# RTL8812AU.net
KiCad netlist of a schematic drawn in Altium Designer
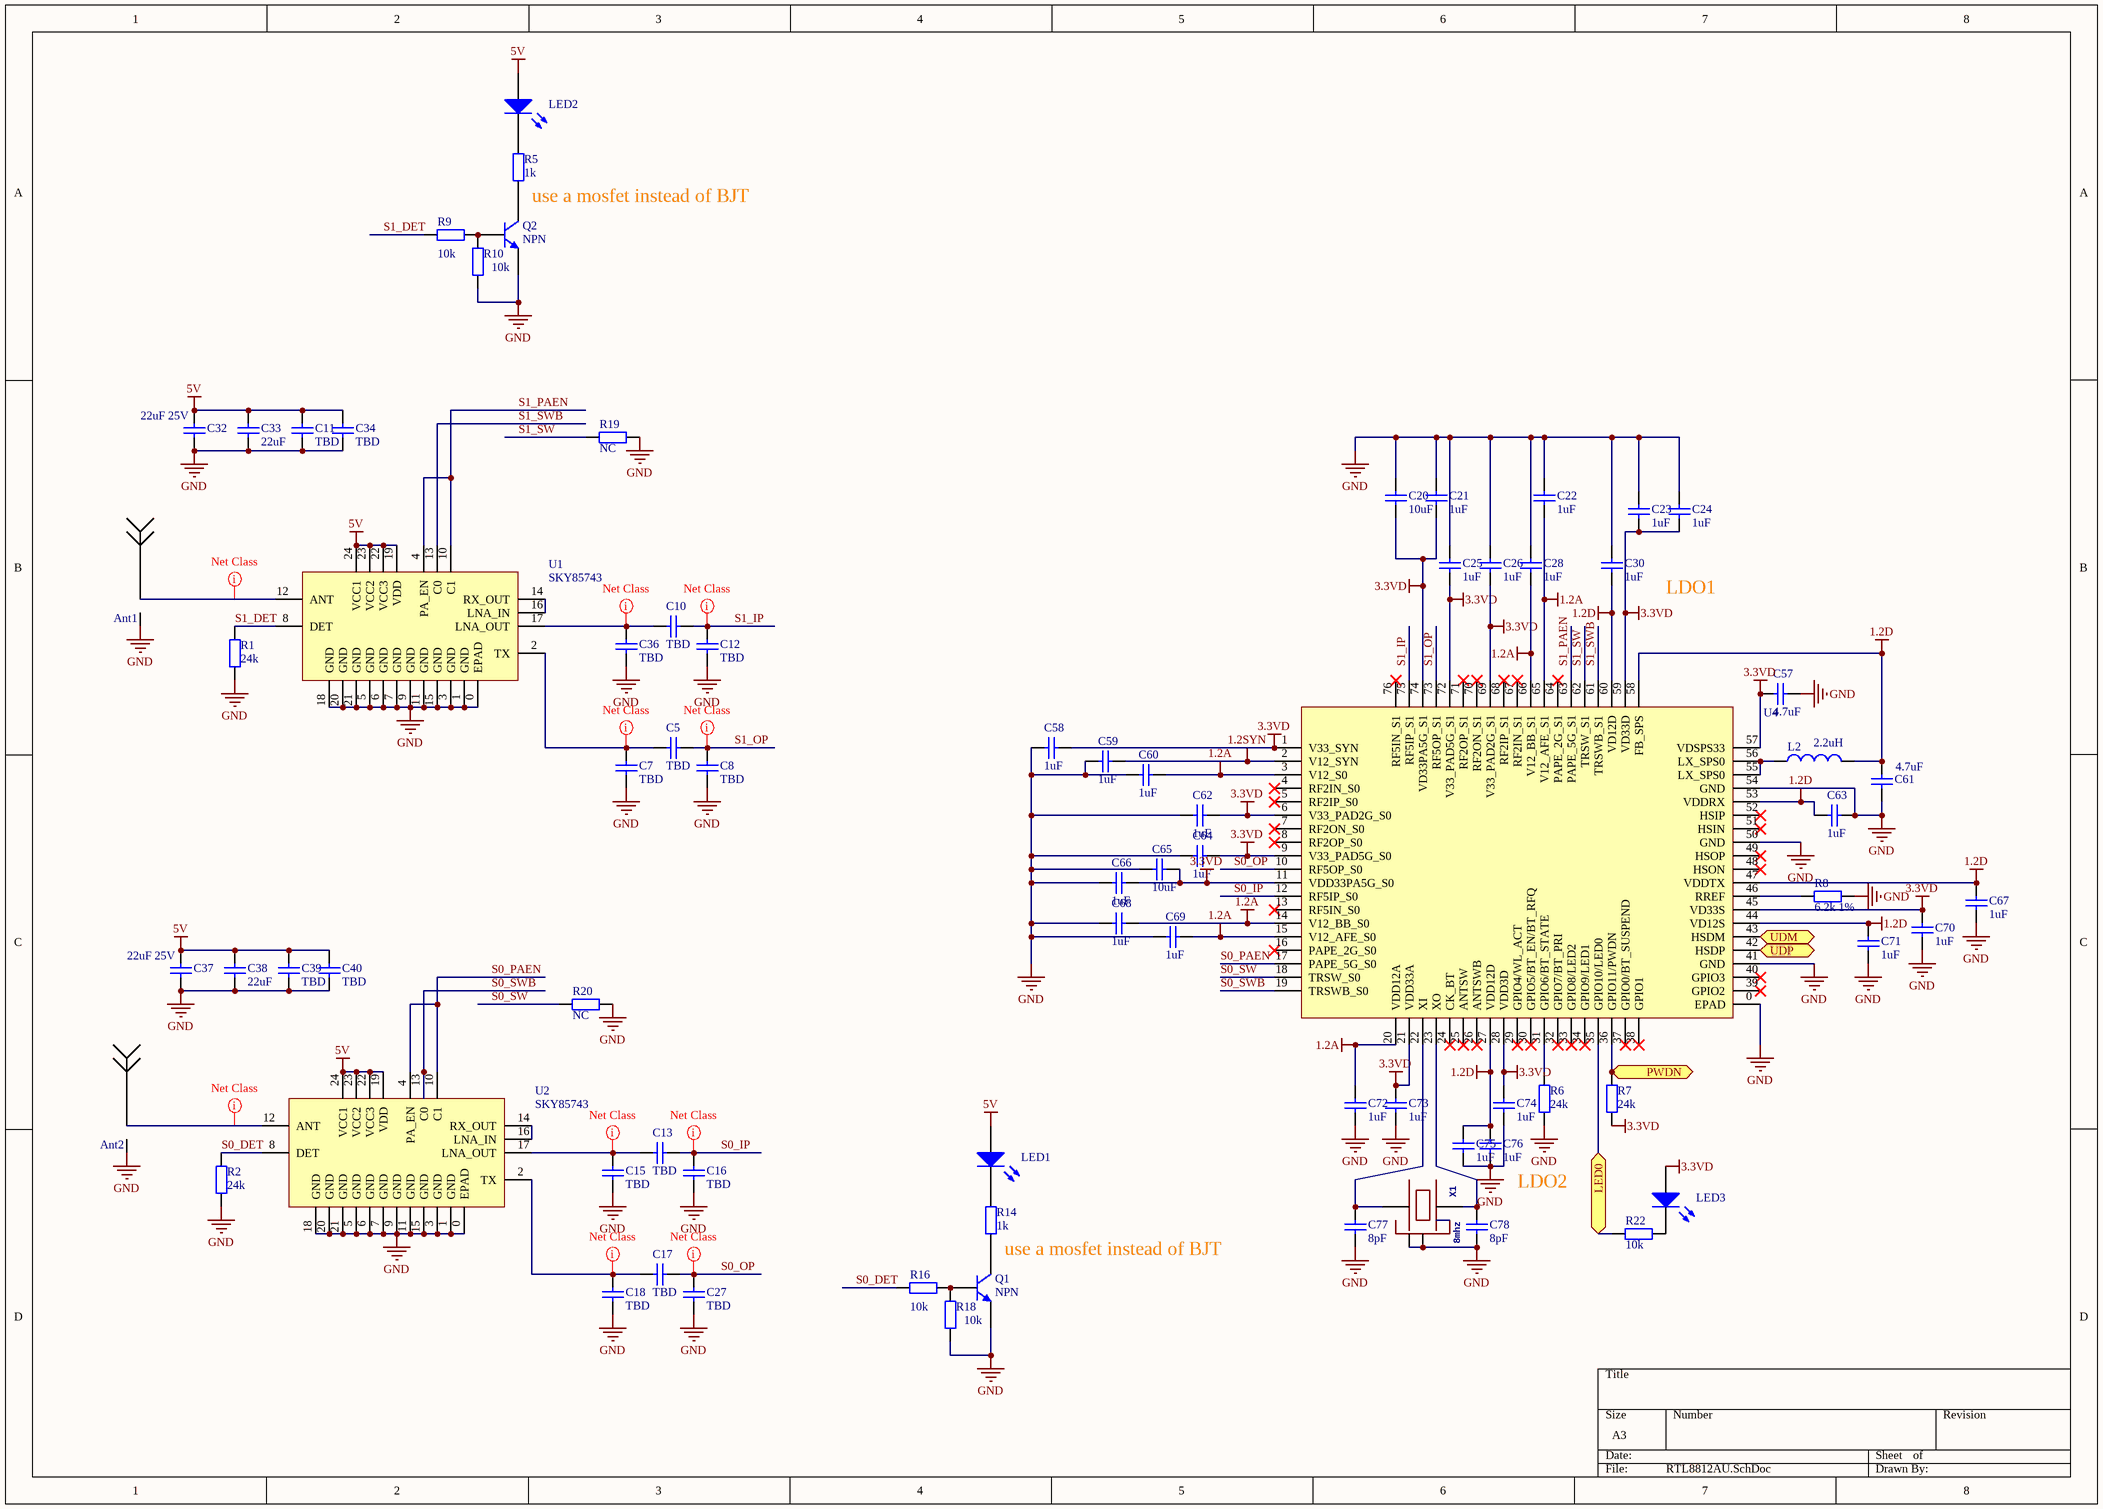
[diagram p0: RTL8812AU.SchDoc]

(export (version "E")
  (design (tool "Eeschema 10.0.6"))
  (components
    (comp (ref "Ant1") (value "Antenna") (footprint "SMA-2") (libsource (lib "F4SDR") (part "Antenna")))
    (comp (ref "Ant2") (value "Antenna") (footprint "SMA-2") (libsource (lib "F4SDR") (part "Antenna")))
    (comp (ref "C5")
      (value "TBD")
      (footprint "0402")
      (description "Capacitor")
      (fields (field (name "PUBLISHER") "Altium Limited"))
      (libsource (lib "RTC6705") (part "Cap"))
    )
    (comp (ref "C7")
      (value "TBD")
      (footprint "0402")
      (description "Capacitor")
      (fields (field (name "PUBLISHER") "Altium Limited"))
      (libsource (lib "RTC6705") (part "Cap"))
    )
    (comp (ref "C8")
      (value "TBD")
      (footprint "0402")
      (description "Capacitor")
      (fields (field (name "PUBLISHER") "Altium Limited"))
      (libsource (lib "RTC6705") (part "Cap"))
    )
    (comp (ref "C10")
      (value "TBD")
      (footprint "0402")
      (description "Capacitor")
      (fields (field (name "PUBLISHER") "Altium Limited"))
      (libsource (lib "RTC6705") (part "Cap"))
    )
    (comp (ref "C11")
      (value "TBD")
      (footprint "0402")
      (description "Capacitor")
      (fields (field (name "PUBLISHER") "Altium Limited"))
      (libsource (lib "RTC6705") (part "Cap"))
    )
    (comp (ref "C12")
      (value "TBD")
      (footprint "0402")
      (description "Capacitor")
      (fields (field (name "PUBLISHER") "Altium Limited"))
      (libsource (lib "RTC6705") (part "Cap"))
    )
    (comp (ref "C13")
      (value "TBD")
      (footprint "0402")
      (description "Capacitor")
      (fields (field (name "PUBLISHER") "Altium Limited"))
      (libsource (lib "RTC6705") (part "Cap"))
    )
    (comp (ref "C15")
      (value "TBD")
      (footprint "0402")
      (description "Capacitor")
      (fields (field (name "PUBLISHER") "Altium Limited"))
      (libsource (lib "RTC6705") (part "Cap"))
    )
    (comp (ref "C16")
      (value "TBD")
      (footprint "0402")
      (description "Capacitor")
      (fields (field (name "PUBLISHER") "Altium Limited"))
      (libsource (lib "RTC6705") (part "Cap"))
    )
    (comp (ref "C17")
      (value "TBD")
      (footprint "0402")
      (description "Capacitor")
      (fields (field (name "PUBLISHER") "Altium Limited"))
      (libsource (lib "RTC6705") (part "Cap"))
    )
    (comp (ref "C18")
      (value "TBD")
      (footprint "0402")
      (description "Capacitor")
      (fields (field (name "PUBLISHER") "Altium Limited"))
      (libsource (lib "RTC6705") (part "Cap"))
    )
    (comp (ref "C20")
      (value "10uF")
      (footprint "0402")
      (description "Capacitor")
      (fields (field (name "PUBLISHER") "Altium Limited"))
      (libsource (lib "RTC6705") (part "Cap"))
    )
    (comp (ref "C21")
      (value "1uF")
      (footprint "0201")
      (description "Capacitor")
      (fields (field (name "PUBLISHER") "Altium Limited"))
      (libsource (lib "RTC6705") (part "Cap"))
    )
    (comp (ref "C22")
      (value "1uF")
      (footprint "0201")
      (description "Capacitor")
      (fields (field (name "PUBLISHER") "Altium Limited"))
      (libsource (lib "RTC6705") (part "Cap"))
    )
    (comp (ref "C23")
      (value "1uF")
      (footprint "0201")
      (description "Capacitor")
      (fields (field (name "PUBLISHER") "Altium Limited"))
      (libsource (lib "RTC6705") (part "Cap"))
    )
    (comp (ref "C24")
      (value "1uF")
      (footprint "0201")
      (description "Capacitor")
      (fields (field (name "PUBLISHER") "Altium Limited"))
      (libsource (lib "RTC6705") (part "Cap"))
    )
    (comp (ref "C25")
      (value "1uF")
      (footprint "0201")
      (description "Capacitor")
      (fields (field (name "PUBLISHER") "Altium Limited"))
      (libsource (lib "RTC6705") (part "Cap"))
    )
    (comp (ref "C26")
      (value "1uF")
      (footprint "0201")
      (description "Capacitor")
      (fields (field (name "PUBLISHER") "Altium Limited"))
      (libsource (lib "RTC6705") (part "Cap"))
    )
    (comp (ref "C27")
      (value "TBD")
      (footprint "0402")
      (description "Capacitor")
      (fields (field (name "PUBLISHER") "Altium Limited"))
      (libsource (lib "RTC6705") (part "Cap"))
    )
    (comp (ref "C28")
      (value "1uF")
      (footprint "0201")
      (description "Capacitor")
      (fields (field (name "PUBLISHER") "Altium Limited"))
      (libsource (lib "RTC6705") (part "Cap"))
    )
    (comp (ref "C30")
      (value "1uF")
      (footprint "0201")
      (description "Capacitor")
      (fields (field (name "PUBLISHER") "Altium Limited"))
      (libsource (lib "RTC6705") (part "Cap"))
    )
    (comp (ref "C32")
      (value "22uF 25V")
      (footprint "1210")
      (description "Capacitor")
      (fields (field (name "Comment") "Cap") (field (name "PUBLISHER") "Altium Limited"))
      (libsource (lib "RTC6705") (part "Cap"))
    )
    (comp (ref "C33")
      (value "22uF")
      (footprint "0805")
      (description "Capacitor")
      (fields (field (name "Comment") "Cap") (field (name "PUBLISHER") "Altium Limited"))
      (libsource (lib "RTC6705") (part "Cap"))
    )
    (comp (ref "C34")
      (value "TBD")
      (footprint "0402")
      (description "Capacitor")
      (fields (field (name "PUBLISHER") "Altium Limited"))
      (libsource (lib "RTC6705") (part "Cap"))
    )
    (comp (ref "C36")
      (value "TBD")
      (footprint "0402")
      (description "Capacitor")
      (fields (field (name "PUBLISHER") "Altium Limited"))
      (libsource (lib "RTC6705") (part "Cap"))
    )
    (comp (ref "C37")
      (value "22uF 25V")
      (footprint "1210")
      (description "Capacitor")
      (fields (field (name "Comment") "Cap") (field (name "PUBLISHER") "Altium Limited"))
      (libsource (lib "RTC6705") (part "Cap"))
    )
    (comp (ref "C38")
      (value "22uF")
      (footprint "0805")
      (description "Capacitor")
      (fields (field (name "Comment") "Cap") (field (name "PUBLISHER") "Altium Limited"))
      (libsource (lib "RTC6705") (part "Cap"))
    )
    (comp (ref "C39")
      (value "TBD")
      (footprint "0402")
      (description "Capacitor")
      (fields (field (name "PUBLISHER") "Altium Limited"))
      (libsource (lib "RTC6705") (part "Cap"))
    )
    (comp (ref "C40")
      (value "TBD")
      (footprint "0402")
      (description "Capacitor")
      (fields (field (name "PUBLISHER") "Altium Limited"))
      (libsource (lib "RTC6705") (part "Cap"))
    )
    (comp (ref "C57")
      (value "4.7uF")
      (footprint "0603")
      (description "Capacitor")
      (fields (field (name "PUBLISHER") "Altium Limited"))
      (libsource (lib "RTC6705") (part "Cap"))
    )
    (comp (ref "C58")
      (value "1uF")
      (footprint "0201")
      (description "Capacitor")
      (fields (field (name "PUBLISHER") "Altium Limited"))
      (libsource (lib "RTC6705") (part "Cap"))
    )
    (comp (ref "C59")
      (value "1uF")
      (footprint "0201")
      (description "Capacitor")
      (fields (field (name "PUBLISHER") "Altium Limited"))
      (libsource (lib "RTC6705") (part "Cap"))
    )
    (comp (ref "C60")
      (value "1uF")
      (footprint "0201")
      (description "Capacitor")
      (fields (field (name "PUBLISHER") "Altium Limited"))
      (libsource (lib "RTC6705") (part "Cap"))
    )
    (comp (ref "C61")
      (value "4.7uF")
      (footprint "0603")
      (description "Capacitor")
      (fields (field (name "PUBLISHER") "Altium Limited"))
      (libsource (lib "RTC6705") (part "Cap"))
    )
    (comp (ref "C62")
      (value "1uF")
      (footprint "0201")
      (description "Capacitor")
      (fields (field (name "PUBLISHER") "Altium Limited"))
      (libsource (lib "RTC6705") (part "Cap"))
    )
    (comp (ref "C63")
      (value "1uF")
      (footprint "0201")
      (description "Capacitor")
      (fields (field (name "PUBLISHER") "Altium Limited"))
      (libsource (lib "RTC6705") (part "Cap"))
    )
    (comp (ref "C64")
      (value "1uF")
      (footprint "0201")
      (description "Capacitor")
      (fields (field (name "PUBLISHER") "Altium Limited"))
      (libsource (lib "RTC6705") (part "Cap"))
    )
    (comp (ref "C65")
      (value "10uF")
      (footprint "0402")
      (description "Capacitor")
      (fields (field (name "PUBLISHER") "Altium Limited"))
      (libsource (lib "RTC6705") (part "Cap"))
    )
    (comp (ref "C66")
      (value "1uF")
      (footprint "0201")
      (description "Capacitor")
      (fields (field (name "PUBLISHER") "Altium Limited"))
      (libsource (lib "RTC6705") (part "Cap"))
    )
    (comp (ref "C67")
      (value "1uF")
      (footprint "0201")
      (description "Capacitor")
      (fields (field (name "PUBLISHER") "Altium Limited"))
      (libsource (lib "RTC6705") (part "Cap"))
    )
    (comp (ref "C68")
      (value "1uF")
      (footprint "0201")
      (description "Capacitor")
      (fields (field (name "PUBLISHER") "Altium Limited"))
      (libsource (lib "RTC6705") (part "Cap"))
    )
    (comp (ref "C69")
      (value "1uF")
      (footprint "0201")
      (description "Capacitor")
      (fields (field (name "PUBLISHER") "Altium Limited"))
      (libsource (lib "RTC6705") (part "Cap"))
    )
    (comp (ref "C70")
      (value "1uF")
      (footprint "0201")
      (description "Capacitor")
      (fields (field (name "PUBLISHER") "Altium Limited"))
      (libsource (lib "RTC6705") (part "Cap"))
    )
    (comp (ref "C71")
      (value "1uF")
      (footprint "0201")
      (description "Capacitor")
      (fields (field (name "PUBLISHER") "Altium Limited"))
      (libsource (lib "RTC6705") (part "Cap"))
    )
    (comp (ref "C72")
      (value "1uF")
      (footprint "0201")
      (description "Capacitor")
      (fields (field (name "PUBLISHER") "Altium Limited"))
      (libsource (lib "RTC6705") (part "Cap"))
    )
    (comp (ref "C73")
      (value "1uF")
      (footprint "0201")
      (description "Capacitor")
      (fields (field (name "PUBLISHER") "Altium Limited"))
      (libsource (lib "RTC6705") (part "Cap"))
    )
    (comp (ref "C74")
      (value "1uF")
      (footprint "0201")
      (description "Capacitor")
      (fields (field (name "PUBLISHER") "Altium Limited"))
      (libsource (lib "RTC6705") (part "Cap"))
    )
    (comp (ref "C75")
      (value "1uF")
      (footprint "0201")
      (description "Capacitor")
      (fields (field (name "PUBLISHER") "Altium Limited"))
      (libsource (lib "RTC6705") (part "Cap"))
    )
    (comp (ref "C76")
      (value "1uF")
      (footprint "0201")
      (description "Capacitor")
      (fields (field (name "PUBLISHER") "Altium Limited"))
      (libsource (lib "RTC6705") (part "Cap"))
    )
    (comp (ref "C77")
      (value "8pF")
      (footprint "0402")
      (description "Capacitor")
      (fields (field (name "PUBLISHER") "Altium Limited"))
      (libsource (lib "RTC6705") (part "Cap"))
    )
    (comp (ref "C78")
      (value "8pF")
      (footprint "0402")
      (description "Capacitor")
      (fields (field (name "PUBLISHER") "Altium Limited"))
      (libsource (lib "RTC6705") (part "Cap"))
    )
    (comp (ref "L2")
      (value "2.2uH")
      (footprint "0806")
      (description "Inductor")
      (fields (field (name "PUBLISHER") "Altium Limited"))
      (libsource (lib "Miscellaneous Devices") (part "Inductor"))
    )
    (comp (ref "LED1")
      (value "LED0")
      (footprint "0603")
      (description "Typical INFRARED GaAs LED")
      (fields (field (name "PUBLISHER") "Altium Limited"))
      (libsource (lib "Miscellaneous Devices") (part "LED0"))
    )
    (comp (ref "LED2")
      (value "LED0")
      (footprint "0603")
      (description "Typical INFRARED GaAs LED")
      (fields (field (name "PUBLISHER") "Altium Limited"))
      (libsource (lib "Miscellaneous Devices") (part "LED0"))
    )
    (comp (ref "LED3")
      (value "LED0")
      (footprint "0603")
      (description "Typical INFRARED GaAs LED")
      (fields (field (name "PUBLISHER") "Altium Limited"))
      (libsource (lib "Miscellaneous Devices") (part "LED0"))
    )
    (comp (ref "Q1")
      (value "NPN")
      (footprint "LC-SOT-323(SC-70)")
      (description "NPN Bipolar Transistor")
      (fields (field (name "PUBLISHER") "Altium Limited"))
      (libsource (lib "BK5811FEM") (part "NPN"))
    )
    (comp (ref "Q2")
      (value "NPN")
      (footprint "LC-SOT-323(SC-70)")
      (description "NPN Bipolar Transistor")
      (fields (field (name "PUBLISHER") "Altium Limited"))
      (libsource (lib "BK5811FEM") (part "NPN"))
    )
    (comp (ref "R1")
      (value "24k")
      (footprint "0402")
      (description "Resistor")
      (fields (field (name "PUBLISHER") "Altium Limited"))
      (libsource (lib "") (part "Res2_3"))
    )
    (comp (ref "R2")
      (value "24k")
      (footprint "0402")
      (description "Resistor")
      (fields (field (name "PUBLISHER") "Altium Limited"))
      (libsource (lib "") (part "Res2_3"))
    )
    (comp (ref "R5")
      (value "1k")
      (footprint "0402")
      (description "Resistor")
      (fields (field (name "Comment") "Res2") (field (name "PUBLISHER") "Altium Limited"))
      (libsource (lib "") (part "Res2_3"))
    )
    (comp (ref "R6")
      (value "24k")
      (footprint "0402")
      (description "Resistor")
      (fields (field (name "PUBLISHER") "Altium Limited"))
      (libsource (lib "") (part "Res2_3"))
    )
    (comp (ref "R7")
      (value "24k")
      (footprint "0402")
      (description "Resistor")
      (fields (field (name "PUBLISHER") "Altium Limited"))
      (libsource (lib "") (part "Res2_3"))
    )
    (comp (ref "R8")
      (value "6.2k 1%")
      (footprint "0402")
      (description "Resistor")
      (fields (field (name "PUBLISHER") "Altium Limited"))
      (libsource (lib "") (part "Res2_2"))
    )
    (comp (ref "R9")
      (value "10k")
      (footprint "0402")
      (description "Resistor")
      (fields (field (name "PUBLISHER") "Altium Limited"))
      (libsource (lib "RTC6705") (part "Res2"))
    )
    (comp (ref "R10")
      (value "10k")
      (footprint "0402")
      (description "Resistor")
      (fields (field (name "PUBLISHER") "Altium Limited"))
      (libsource (lib "") (part "Res2_1"))
    )
    (comp (ref "R14")
      (value "1k")
      (footprint "0402")
      (description "Resistor")
      (fields (field (name "Comment") "Res2") (field (name "PUBLISHER") "Altium Limited"))
      (libsource (lib "") (part "Res2_3"))
    )
    (comp (ref "R16")
      (value "10k")
      (footprint "0402")
      (description "Resistor")
      (fields (field (name "PUBLISHER") "Altium Limited"))
      (libsource (lib "RTC6705") (part "Res2"))
    )
    (comp (ref "R18")
      (value "10k")
      (footprint "0402")
      (description "Resistor")
      (fields (field (name "PUBLISHER") "Altium Limited"))
      (libsource (lib "") (part "Res2_1"))
    )
    (comp (ref "R19")
      (value "NC")
      (footprint "0402")
      (description "Resistor")
      (fields (field (name "Comment") "Res2") (field (name "PUBLISHER") "Altium Limited"))
      (libsource (lib "RTC6705") (part "Res2"))
    )
    (comp (ref "R20")
      (value "NC")
      (footprint "0402")
      (description "Resistor")
      (fields (field (name "Comment") "Res2") (field (name "PUBLISHER") "Altium Limited"))
      (libsource (lib "RTC6705") (part "Res2"))
    )
    (comp (ref "R22")
      (value "10k")
      (footprint "0402")
      (description "Resistor")
      (fields (field (name "PUBLISHER") "Altium Limited"))
      (libsource (lib "Miscellaneous Devices") (part "Res2"))
    )
    (comp (ref "U1")
      (value "SKY85743")
      (footprint "SKY85743")
      (libsource (lib "RTL8812AU") (part "SKY85743"))
    )
    (comp (ref "U2")
      (value "SKY85743")
      (footprint "SKY85743")
      (libsource (lib "RTL8812AU") (part "SKY85743"))
    )
    (comp (ref "U4")
      (value "RTL8812AU")
      (footprint "RTL8812AU")
      (libsource (lib "RTL8812AU") (part "RTL8812AU"))
    )
    (comp (ref "X1")
      (value "8mhz")
      (footprint "OSCILLATOR-3.2X2.5")
      (description "Crystal Oscillator in 3.2x2.5 SMD")
      (libsource (lib "sch") (part "OSCILLATOR-3.2X2.5"))
    )
  )
  (nets
    (net (code "1") (name "/LED0") (class "Default")
      (node (ref "R22") (pin "1") (pinfunction "1_1") (pintype "passive"))
      (node (ref "U4") (pin "35") (pinfunction "GPIO10/LED0_35") (pintype "passive"))
    )
    (net (code "2") (name "/PWDN") (class "Default")
      (node (ref "R7") (pin "1") (pinfunction "1_1") (pintype "passive"))
      (node (ref "U4") (pin "36") (pinfunction "GPIO11/PWDN_36") (pintype "passive"))
    )
    (net (code "3") (name "/S0_DET") (class "Default")
      (node (ref "R16") (pin "1") (pinfunction "1_1") (pintype "passive"))
      (node (ref "R2") (pin "1") (pinfunction "1_1") (pintype "passive"))
      (node (ref "U2") (pin "8") (pinfunction "DET_8") (pintype "passive"))
    )
    (net (code "4") (name "/S0_IP") (class "Default")
      (node (ref "C13") (pin "1") (pinfunction "1_1") (pintype "passive"))
      (node (ref "C16") (pin "2") (pinfunction "2_2") (pintype "passive"))
      (node (ref "U4") (pin "12") (pinfunction "RF5IP_S0_12") (pintype "passive"))
    )
    (net (code "5") (name "/S0_OP") (class "Default")
      (node (ref "C17") (pin "1") (pinfunction "1_1") (pintype "passive"))
      (node (ref "C27") (pin "2") (pinfunction "2_2") (pintype "passive"))
      (node (ref "U4") (pin "10") (pinfunction "RF5OP_S0_10") (pintype "passive"))
    )
    (net (code "6") (name "/S0_PAEN") (class "Default")
      (node (ref "U2") (pin "10") (pinfunction "C1_10") (pintype "passive"))
      (node (ref "U2") (pin "4") (pinfunction "PA_EN_4") (pintype "passive"))
      (node (ref "U4") (pin "17") (pinfunction "PAPE_5G_S0_17") (pintype "passive"))
    )
    (net (code "7") (name "/S0_SW") (class "Default")
      (node (ref "R20") (pin "1") (pinfunction "1_1") (pintype "passive"))
      (node (ref "U4") (pin "18") (pinfunction "TRSW_S0_18") (pintype "passive"))
    )
    (net (code "8") (name "/S0_SWB") (class "Default")
      (node (ref "U2") (pin "13") (pinfunction "C0_13") (pintype "passive"))
      (node (ref "U4") (pin "19") (pinfunction "TRSWB_S0_19") (pintype "passive"))
    )
    (net (code "9") (name "/S1_DET") (class "Default")
      (node (ref "R1") (pin "1") (pinfunction "1_1") (pintype "passive"))
      (node (ref "R9") (pin "1") (pinfunction "1_1") (pintype "passive"))
      (node (ref "U1") (pin "8") (pinfunction "DET_8") (pintype "passive"))
    )
    (net (code "10") (name "/S1_IP") (class "Default")
      (node (ref "C10") (pin "1") (pinfunction "1_1") (pintype "passive"))
      (node (ref "C12") (pin "2") (pinfunction "2_2") (pintype "passive"))
      (node (ref "U4") (pin "75") (pinfunction "RF5IP_S1_75") (pintype "passive"))
    )
    (net (code "11") (name "/S1_OP") (class "Default")
      (node (ref "C5") (pin "1") (pinfunction "1_1") (pintype "passive"))
      (node (ref "C8") (pin "2") (pinfunction "2_2") (pintype "passive"))
      (node (ref "U4") (pin "73") (pinfunction "RF5OP_S1_73") (pintype "passive"))
    )
    (net (code "12") (name "/S1_PAEN") (class "Default")
      (node (ref "U1") (pin "10") (pinfunction "C1_10") (pintype "passive"))
      (node (ref "U1") (pin "4") (pinfunction "PA_EN_4") (pintype "passive"))
      (node (ref "U4") (pin "63") (pinfunction "PAPE_5G_S1_63") (pintype "passive"))
    )
    (net (code "13") (name "/S1_SW") (class "Default")
      (node (ref "R19") (pin "1") (pinfunction "1_1") (pintype "passive"))
      (node (ref "U4") (pin "62") (pinfunction "TRSW_S1_62") (pintype "passive"))
    )
    (net (code "14") (name "/S1_SWB") (class "Default")
      (node (ref "U1") (pin "13") (pinfunction "C0_13") (pintype "passive"))
      (node (ref "U4") (pin "61") (pinfunction "TRSWB_S1_61") (pintype "passive"))
    )
    (net (code "15") (name "/UDM") (class "Default")
      (node (ref "U4") (pin "43") (pinfunction "HSDM_43") (pintype "passive"))
    )
    (net (code "16") (name "/UDP") (class "Default")
      (node (ref "U4") (pin "42") (pinfunction "HSDP_42") (pintype "passive"))
    )
    (net (code "17") (name "1.2A") (class "Default")
      (node (ref "C22") (pin "2") (pinfunction "2_2") (pintype "passive"))
      (node (ref "C28") (pin "2") (pinfunction "2_2") (pintype "passive"))
      (node (ref "C60") (pin "2") (pinfunction "2_2") (pintype "passive"))
      (node (ref "C68") (pin "2") (pinfunction "2_2") (pintype "passive"))
      (node (ref "C69") (pin "2") (pinfunction "2_2") (pintype "passive"))
      (node (ref "C72") (pin "1") (pinfunction "1_1") (pintype "passive"))
      (node (ref "U4") (pin "14") (pinfunction "V12_BB_S0_14") (pintype "passive"))
      (node (ref "U4") (pin "15") (pinfunction "V12_AFE_S0_15") (pintype "passive"))
      (node (ref "U4") (pin "20") (pinfunction "VDD12A_20") (pintype "passive"))
      (node (ref "U4") (pin "3") (pinfunction "V12_S0_3") (pintype "passive"))
      (node (ref "U4") (pin "65") (pinfunction "V12_AFE_S1_65") (pintype "passive"))
      (node (ref "U4") (pin "66") (pinfunction "V12_BB_S1_66") (pintype "passive"))
    )
    (net (code "18") (name "1.2D") (class "Default")
      (node (ref "C30") (pin "2") (pinfunction "2_2") (pintype "passive"))
      (node (ref "C61") (pin "2") (pinfunction "2_2") (pintype "passive"))
      (node (ref "C63") (pin "2") (pinfunction "2_2") (pintype "passive"))
      (node (ref "C67") (pin "1") (pinfunction "1_1") (pintype "passive"))
      (node (ref "C71") (pin "1") (pinfunction "1_1") (pintype "passive"))
      (node (ref "C75") (pin "1") (pinfunction "1_1") (pintype "passive"))
      (node (ref "C76") (pin "2") (pinfunction "2_2") (pintype "passive"))
      (node (ref "L2") (pin "2") (pinfunction "2_2") (pintype "passive"))
      (node (ref "U4") (pin "27") (pinfunction "VDD12D_27") (pintype "passive"))
      (node (ref "U4") (pin "44") (pinfunction "VD12S_44") (pintype "passive"))
      (node (ref "U4") (pin "47") (pinfunction "VDDTX_47") (pintype "passive"))
      (node (ref "U4") (pin "53") (pinfunction "VDDRX_53") (pintype "passive"))
      (node (ref "U4") (pin "58") (pinfunction "FB_SPS_58") (pintype "passive"))
      (node (ref "U4") (pin "60") (pinfunction "VD12D_60") (pintype "passive"))
    )
    (net (code "19") (name "1.2SYN") (class "Default")
      (node (ref "C59") (pin "2") (pinfunction "2_2") (pintype "passive"))
      (node (ref "U4") (pin "2") (pinfunction "V12_SYN_2") (pintype "passive"))
    )
    (net (code "20") (name "3.3VD") (class "Default")
      (node (ref "C20") (pin "1") (pinfunction "1_1") (pintype "passive"))
      (node (ref "C21") (pin "2") (pinfunction "2_2") (pintype "passive"))
      (node (ref "C23") (pin "2") (pinfunction "2_2") (pintype "passive"))
      (node (ref "C24") (pin "2") (pinfunction "2_2") (pintype "passive"))
      (node (ref "C25") (pin "2") (pinfunction "2_2") (pintype "passive"))
      (node (ref "C26") (pin "2") (pinfunction "2_2") (pintype "passive"))
      (node (ref "C57") (pin "2") (pinfunction "2_2") (pintype "passive"))
      (node (ref "C58") (pin "2") (pinfunction "2_2") (pintype "passive"))
      (node (ref "C62") (pin "2") (pinfunction "2_2") (pintype "passive"))
      (node (ref "C64") (pin "2") (pinfunction "2_2") (pintype "passive"))
      (node (ref "C65") (pin "2") (pinfunction "2_2") (pintype "passive"))
      (node (ref "C66") (pin "2") (pinfunction "2_2") (pintype "passive"))
      (node (ref "C70") (pin "1") (pinfunction "1_1") (pintype "passive"))
      (node (ref "C73") (pin "1") (pinfunction "1_1") (pintype "passive"))
      (node (ref "C74") (pin "1") (pinfunction "1_1") (pintype "passive"))
      (node (ref "LED3") (pin "1") (pinfunction "A_1") (pintype "passive"))
      (node (ref "R7") (pin "2") (pinfunction "2_2") (pintype "passive"))
      (node (ref "U4") (pin "1") (pinfunction "V33_SYN_1") (pintype "passive"))
      (node (ref "U4") (pin "11") (pinfunction "VDD33PA5G_S0_11") (pintype "passive"))
      (node (ref "U4") (pin "21") (pinfunction "VDD33A_21") (pintype "passive"))
      (node (ref "U4") (pin "28") (pinfunction "VDD3D_28") (pintype "passive"))
      (node (ref "U4") (pin "45") (pinfunction "VD33S_45") (pintype "passive"))
      (node (ref "U4") (pin "57") (pinfunction "VDSPS33_57") (pintype "passive"))
      (node (ref "U4") (pin "59") (pinfunction "VD33D_59") (pintype "passive"))
      (node (ref "U4") (pin "6") (pinfunction "V33_PAD2G_S0_6") (pintype "passive"))
      (node (ref "U4") (pin "69") (pinfunction "V33_PAD2G_S1_69") (pintype "passive"))
      (node (ref "U4") (pin "72") (pinfunction "V33_PAD5G_S1_72") (pintype "passive"))
      (node (ref "U4") (pin "74") (pinfunction "VD33PA5G_S1_74") (pintype "passive"))
      (node (ref "U4") (pin "9") (pinfunction "V33_PAD5G_S0_9") (pintype "passive"))
    )
    (net (code "21") (name "5V") (class "Default")
      (node (ref "C11") (pin "2") (pinfunction "2_2") (pintype "passive"))
      (node (ref "C32") (pin "2") (pinfunction "2_2") (pintype "passive"))
      (node (ref "C33") (pin "2") (pinfunction "2_2") (pintype "passive"))
      (node (ref "C34") (pin "2") (pinfunction "2_2") (pintype "passive"))
      (node (ref "C37") (pin "2") (pinfunction "2_2") (pintype "passive"))
      (node (ref "C38") (pin "2") (pinfunction "2_2") (pintype "passive"))
      (node (ref "C39") (pin "2") (pinfunction "2_2") (pintype "passive"))
      (node (ref "C40") (pin "2") (pinfunction "2_2") (pintype "passive"))
      (node (ref "LED1") (pin "1") (pinfunction "A_1") (pintype "passive"))
      (node (ref "LED2") (pin "1") (pinfunction "A_1") (pintype "passive"))
      (node (ref "U1") (pin "19") (pinfunction "VDD_19") (pintype "passive"))
      (node (ref "U1") (pin "22") (pinfunction "VCC3_22") (pintype "passive"))
      (node (ref "U1") (pin "23") (pinfunction "VCC2_23") (pintype "passive"))
      (node (ref "U1") (pin "24") (pinfunction "VCC1_24") (pintype "passive"))
      (node (ref "U2") (pin "19") (pinfunction "VDD_19") (pintype "passive"))
      (node (ref "U2") (pin "22") (pinfunction "VCC3_22") (pintype "passive"))
      (node (ref "U2") (pin "23") (pinfunction "VCC2_23") (pintype "passive"))
      (node (ref "U2") (pin "24") (pinfunction "VCC1_24") (pintype "passive"))
    )
    (net (code "22") (name "GND") (class "Default")
      (node (ref "Ant1") (pin "GND") (pinfunction "G_GND") (pintype "passive"))
      (node (ref "Ant2") (pin "GND") (pinfunction "G_GND") (pintype "passive"))
      (node (ref "C11") (pin "1") (pinfunction "1_1") (pintype "passive"))
      (node (ref "C12") (pin "1") (pinfunction "1_1") (pintype "passive"))
      (node (ref "C15") (pin "1") (pinfunction "1_1") (pintype "passive"))
      (node (ref "C16") (pin "1") (pinfunction "1_1") (pintype "passive"))
      (node (ref "C18") (pin "1") (pinfunction "1_1") (pintype "passive"))
      (node (ref "C20") (pin "2") (pinfunction "2_2") (pintype "passive"))
      (node (ref "C21") (pin "1") (pinfunction "1_1") (pintype "passive"))
      (node (ref "C22") (pin "1") (pinfunction "1_1") (pintype "passive"))
      (node (ref "C23") (pin "1") (pinfunction "1_1") (pintype "passive"))
      (node (ref "C24") (pin "1") (pinfunction "1_1") (pintype "passive"))
      (node (ref "C25") (pin "1") (pinfunction "1_1") (pintype "passive"))
      (node (ref "C26") (pin "1") (pinfunction "1_1") (pintype "passive"))
      (node (ref "C27") (pin "1") (pinfunction "1_1") (pintype "passive"))
      (node (ref "C28") (pin "1") (pinfunction "1_1") (pintype "passive"))
      (node (ref "C30") (pin "1") (pinfunction "1_1") (pintype "passive"))
      (node (ref "C32") (pin "1") (pinfunction "1_1") (pintype "passive"))
      (node (ref "C33") (pin "1") (pinfunction "1_1") (pintype "passive"))
      (node (ref "C34") (pin "1") (pinfunction "1_1") (pintype "passive"))
      (node (ref "C36") (pin "1") (pinfunction "1_1") (pintype "passive"))
      (node (ref "C37") (pin "1") (pinfunction "1_1") (pintype "passive"))
      (node (ref "C38") (pin "1") (pinfunction "1_1") (pintype "passive"))
      (node (ref "C39") (pin "1") (pinfunction "1_1") (pintype "passive"))
      (node (ref "C40") (pin "1") (pinfunction "1_1") (pintype "passive"))
      (node (ref "C57") (pin "1") (pinfunction "1_1") (pintype "passive"))
      (node (ref "C58") (pin "1") (pinfunction "1_1") (pintype "passive"))
      (node (ref "C59") (pin "1") (pinfunction "1_1") (pintype "passive"))
      (node (ref "C60") (pin "1") (pinfunction "1_1") (pintype "passive"))
      (node (ref "C61") (pin "1") (pinfunction "1_1") (pintype "passive"))
      (node (ref "C62") (pin "1") (pinfunction "1_1") (pintype "passive"))
      (node (ref "C63") (pin "1") (pinfunction "1_1") (pintype "passive"))
      (node (ref "C64") (pin "1") (pinfunction "1_1") (pintype "passive"))
      (node (ref "C65") (pin "1") (pinfunction "1_1") (pintype "passive"))
      (node (ref "C66") (pin "1") (pinfunction "1_1") (pintype "passive"))
      (node (ref "C67") (pin "2") (pinfunction "2_2") (pintype "passive"))
      (node (ref "C68") (pin "1") (pinfunction "1_1") (pintype "passive"))
      (node (ref "C69") (pin "1") (pinfunction "1_1") (pintype "passive"))
      (node (ref "C7") (pin "1") (pinfunction "1_1") (pintype "passive"))
      (node (ref "C70") (pin "2") (pinfunction "2_2") (pintype "passive"))
      (node (ref "C71") (pin "2") (pinfunction "2_2") (pintype "passive"))
      (node (ref "C72") (pin "2") (pinfunction "2_2") (pintype "passive"))
      (node (ref "C73") (pin "2") (pinfunction "2_2") (pintype "passive"))
      (node (ref "C74") (pin "2") (pinfunction "2_2") (pintype "passive"))
      (node (ref "C75") (pin "2") (pinfunction "2_2") (pintype "passive"))
      (node (ref "C76") (pin "1") (pinfunction "1_1") (pintype "passive"))
      (node (ref "C77") (pin "1") (pinfunction "1_1") (pintype "passive"))
      (node (ref "C78") (pin "2") (pinfunction "2_2") (pintype "passive"))
      (node (ref "C8") (pin "1") (pinfunction "1_1") (pintype "passive"))
      (node (ref "Q1") (pin "2") (pinfunction "E_2") (pintype "passive"))
      (node (ref "Q2") (pin "2") (pinfunction "E_2") (pintype "passive"))
      (node (ref "R1") (pin "2") (pinfunction "2_2") (pintype "passive"))
      (node (ref "R10") (pin "1") (pinfunction "1_1") (pintype "passive"))
      (node (ref "R18") (pin "1") (pinfunction "1_1") (pintype "passive"))
      (node (ref "R19") (pin "2") (pinfunction "2_2") (pintype "passive"))
      (node (ref "R2") (pin "2") (pinfunction "2_2") (pintype "passive"))
      (node (ref "R20") (pin "2") (pinfunction "2_2") (pintype "passive"))
      (node (ref "R6") (pin "2") (pinfunction "2_2") (pintype "passive"))
      (node (ref "R8") (pin "1") (pinfunction "1_1") (pintype "passive"))
      (node (ref "U1") (pin "0") (pinfunction "EPAD_0") (pintype "passive"))
      (node (ref "U1") (pin "1") (pinfunction "GND_1") (pintype "passive"))
      (node (ref "U1") (pin "11") (pinfunction "GND_11") (pintype "passive"))
      (node (ref "U1") (pin "15") (pinfunction "GND_15") (pintype "passive"))
      (node (ref "U1") (pin "18") (pinfunction "GND_18") (pintype "passive"))
      (node (ref "U1") (pin "20") (pinfunction "GND_20") (pintype "passive"))
      (node (ref "U1") (pin "21") (pinfunction "GND_21") (pintype "passive"))
      (node (ref "U1") (pin "3") (pinfunction "GND_3") (pintype "passive"))
      (node (ref "U1") (pin "5") (pinfunction "GND_5") (pintype "passive"))
      (node (ref "U1") (pin "6") (pinfunction "GND_6") (pintype "passive"))
      (node (ref "U1") (pin "7") (pinfunction "GND_7") (pintype "passive"))
      (node (ref "U1") (pin "9") (pinfunction "GND_9") (pintype "passive"))
      (node (ref "U2") (pin "0") (pinfunction "EPAD_0") (pintype "passive"))
      (node (ref "U2") (pin "1") (pinfunction "GND_1") (pintype "passive"))
      (node (ref "U2") (pin "11") (pinfunction "GND_11") (pintype "passive"))
      (node (ref "U2") (pin "15") (pinfunction "GND_15") (pintype "passive"))
      (node (ref "U2") (pin "18") (pinfunction "GND_18") (pintype "passive"))
      (node (ref "U2") (pin "20") (pinfunction "GND_20") (pintype "passive"))
      (node (ref "U2") (pin "21") (pinfunction "GND_21") (pintype "passive"))
      (node (ref "U2") (pin "3") (pinfunction "GND_3") (pintype "passive"))
      (node (ref "U2") (pin "5") (pinfunction "GND_5") (pintype "passive"))
      (node (ref "U2") (pin "6") (pinfunction "GND_6") (pintype "passive"))
      (node (ref "U2") (pin "7") (pinfunction "GND_7") (pintype "passive"))
      (node (ref "U2") (pin "9") (pinfunction "GND_9") (pintype "passive"))
      (node (ref "U4") (pin "0") (pinfunction "EPAD_0") (pintype "passive"))
      (node (ref "U4") (pin "41") (pinfunction "GND_41") (pintype "passive"))
      (node (ref "U4") (pin "50") (pinfunction "GND_50") (pintype "passive"))
      (node (ref "U4") (pin "54") (pinfunction "GND_54") (pintype "passive"))
      (node (ref "X1") (pin "2") (pinfunction "NC_2_2") (pintype "open_emitter"))
      (node (ref "X1") (pin "4") (pinfunction "NC_4_4") (pintype "open_emitter"))
    )
    (net (code "23") (name "Net-(L2-Pad1)") (class "Default")
      (node (ref "L2") (pin "1") (pinfunction "1_1") (pintype "passive"))
      (node (ref "U4") (pin "55") (pinfunction "LX_SPS0_55") (pintype "passive"))
      (node (ref "U4") (pin "56") (pinfunction "LX_SPS0_56") (pintype "passive"))
    )
    (net (code "24") (name "Net-(LED1-K)") (class "Default")
      (node (ref "LED1") (pin "2") (pinfunction "K_2") (pintype "passive"))
      (node (ref "R14") (pin "1") (pinfunction "1_1") (pintype "passive"))
    )
    (net (code "25") (name "Net-(LED2-K)") (class "Default")
      (node (ref "LED2") (pin "2") (pinfunction "K_2") (pintype "passive"))
      (node (ref "R5") (pin "1") (pinfunction "1_1") (pintype "passive"))
    )
    (net (code "26") (name "Net-(LED3-K)") (class "Default")
      (node (ref "LED3") (pin "2") (pinfunction "K_2") (pintype "passive"))
      (node (ref "R22") (pin "2") (pinfunction "2_2") (pintype "passive"))
    )
    (net (code "27") (name "Net-(Q1-B)") (class "Default")
      (node (ref "Q1") (pin "1") (pinfunction "B_1") (pintype "passive"))
      (node (ref "R16") (pin "2") (pinfunction "2_2") (pintype "passive"))
      (node (ref "R18") (pin "2") (pinfunction "2_2") (pintype "passive"))
    )
    (net (code "28") (name "Net-(Q1-C)") (class "Default")
      (node (ref "Q1") (pin "3") (pinfunction "C_3") (pintype "passive"))
      (node (ref "R14") (pin "2") (pinfunction "2_2") (pintype "passive"))
    )
    (net (code "29") (name "Net-(Q2-B)") (class "Default")
      (node (ref "Q2") (pin "1") (pinfunction "B_1") (pintype "passive"))
      (node (ref "R10") (pin "2") (pinfunction "2_2") (pintype "passive"))
      (node (ref "R9") (pin "2") (pinfunction "2_2") (pintype "passive"))
    )
    (net (code "30") (name "Net-(Q2-C)") (class "Default")
      (node (ref "Q2") (pin "3") (pinfunction "C_3") (pintype "passive"))
      (node (ref "R5") (pin "2") (pinfunction "2_2") (pintype "passive"))
    )
    (net (code "31") (name "Net-(U1-ANT)") (class "Default")
      (node (ref "Ant1") (pin "1") (pinfunction "1_1") (pintype "passive"))
      (node (ref "U1") (pin "12") (pinfunction "ANT_12") (pintype "passive"))
    )
    (net (code "32") (name "Net-(U1-LNA_IN)") (class "Default")
      (node (ref "U1") (pin "14") (pinfunction "RX_OUT_14") (pintype "passive"))
      (node (ref "U1") (pin "16") (pinfunction "LNA_IN_16") (pintype "passive"))
    )
    (net (code "33") (name "Net-(U1-LNA_OUT)") (class "Default")
      (node (ref "C10") (pin "2") (pinfunction "2_2") (pintype "passive"))
      (node (ref "C36") (pin "2") (pinfunction "2_2") (pintype "passive"))
      (node (ref "U1") (pin "17") (pinfunction "LNA_OUT_17") (pintype "passive"))
    )
    (net (code "34") (name "Net-(U1-TX)") (class "Default")
      (node (ref "C5") (pin "2") (pinfunction "2_2") (pintype "passive"))
      (node (ref "C7") (pin "2") (pinfunction "2_2") (pintype "passive"))
      (node (ref "U1") (pin "2") (pinfunction "TX_2") (pintype "passive"))
    )
    (net (code "35") (name "Net-(U2-ANT)") (class "Default")
      (node (ref "Ant2") (pin "1") (pinfunction "1_1") (pintype "passive"))
      (node (ref "U2") (pin "12") (pinfunction "ANT_12") (pintype "passive"))
    )
    (net (code "36") (name "Net-(U2-LNA_IN)") (class "Default")
      (node (ref "U2") (pin "14") (pinfunction "RX_OUT_14") (pintype "passive"))
      (node (ref "U2") (pin "16") (pinfunction "LNA_IN_16") (pintype "passive"))
    )
    (net (code "37") (name "Net-(U2-LNA_OUT)") (class "Default")
      (node (ref "C13") (pin "2") (pinfunction "2_2") (pintype "passive"))
      (node (ref "C15") (pin "2") (pinfunction "2_2") (pintype "passive"))
      (node (ref "U2") (pin "17") (pinfunction "LNA_OUT_17") (pintype "passive"))
    )
    (net (code "38") (name "Net-(U2-TX)") (class "Default")
      (node (ref "C17") (pin "2") (pinfunction "2_2") (pintype "passive"))
      (node (ref "C18") (pin "2") (pinfunction "2_2") (pintype "passive"))
      (node (ref "U2") (pin "2") (pinfunction "TX_2") (pintype "passive"))
    )
    (net (code "39") (name "Net-(U4-GPIO6{slash}BT_STATE)") (class "Default")
      (node (ref "R6") (pin "1") (pinfunction "1_1") (pintype "passive"))
      (node (ref "U4") (pin "31") (pinfunction "GPIO6/BT_STATE_31") (pintype "passive"))
    )
    (net (code "40") (name "Net-(U4-RREF)") (class "Default")
      (node (ref "R8") (pin "2") (pinfunction "2_2") (pintype "passive"))
      (node (ref "U4") (pin "46") (pinfunction "RREF_46") (pintype "passive"))
    )
    (net (code "41") (name "Net-(U4-XI)") (class "Default")
      (node (ref "C77") (pin "2") (pinfunction "2_2") (pintype "passive"))
      (node (ref "U4") (pin "22") (pinfunction "XI_22") (pintype "passive"))
      (node (ref "X1") (pin "1") (pinfunction "1_1") (pintype "passive"))
    )
    (net (code "42") (name "Net-(U4-XO)") (class "Default")
      (node (ref "C78") (pin "1") (pinfunction "1_1") (pintype "passive"))
      (node (ref "U4") (pin "23") (pinfunction "XO_23") (pintype "passive"))
      (node (ref "X1") (pin "3") (pinfunction "3_3") (pintype "passive"))
    )
    (net (code "43") (name "unconnected-(U4-ANTSW-Pad25)") (class "Default")
      (node (ref "U4") (pin "25") (pinfunction "ANTSW_25") (pintype "passive+no_connect"))
    )
    (net (code "44") (name "unconnected-(U4-ANTSWB-Pad26)") (class "Default")
      (node (ref "U4") (pin "26") (pinfunction "ANTSWB_26") (pintype "passive+no_connect"))
    )
    (net (code "45") (name "unconnected-(U4-CK_BT-Pad24)") (class "Default")
      (node (ref "U4") (pin "24") (pinfunction "CK_BT_24") (pintype "passive+no_connect"))
    )
    (net (code "46") (name "unconnected-(U4-GPIO0{slash}BT_SUSPEND-Pad37)") (class "Default")
      (node (ref "U4") (pin "37") (pinfunction "GPIO0/BT_SUSPEND_37") (pintype "passive+no_connect"))
    )
    (net (code "47") (name "unconnected-(U4-GPIO1-Pad38)") (class "Default")
      (node (ref "U4") (pin "38") (pinfunction "GPIO1_38") (pintype "passive+no_connect"))
    )
    (net (code "48") (name "unconnected-(U4-GPIO2-Pad39)") (class "Default")
      (node (ref "U4") (pin "39") (pinfunction "GPIO2_39") (pintype "passive+no_connect"))
    )
    (net (code "49") (name "unconnected-(U4-GPIO3-Pad40)") (class "Default")
      (node (ref "U4") (pin "40") (pinfunction "GPIO3_40") (pintype "passive+no_connect"))
    )
    (net (code "50") (name "unconnected-(U4-GPIO4{slash}WL_ACT-Pad29)") (class "Default")
      (node (ref "U4") (pin "29") (pinfunction "GPIO4/WL_ACT_29") (pintype "passive+no_connect"))
    )
    (net (code "51") (name "unconnected-(U4-GPIO5{slash}BT_EN{slash}BT_RFQ-Pad30)") (class "Default")
      (node (ref "U4") (pin "30") (pinfunction "GPIO5/BT_EN/BT_RFQ_30") (pintype "passive+no_connect"))
    )
    (net (code "52") (name "unconnected-(U4-GPIO7{slash}BT_PRI-Pad32)") (class "Default")
      (node (ref "U4") (pin "32") (pinfunction "GPIO7/BT_PRI_32") (pintype "passive+no_connect"))
    )
    (net (code "53") (name "unconnected-(U4-GPIO8{slash}LED2-Pad33)") (class "Default")
      (node (ref "U4") (pin "33") (pinfunction "GPIO8/LED2_33") (pintype "passive+no_connect"))
    )
    (net (code "54") (name "unconnected-(U4-GPIO9{slash}LED1-Pad34)") (class "Default")
      (node (ref "U4") (pin "34") (pinfunction "GPIO9/LED1_34") (pintype "passive+no_connect"))
    )
    (net (code "55") (name "unconnected-(U4-HSIN-Pad51)") (class "Default")
      (node (ref "U4") (pin "51") (pinfunction "HSIN_51") (pintype "passive+no_connect"))
    )
    (net (code "56") (name "unconnected-(U4-HSIP-Pad52)") (class "Default")
      (node (ref "U4") (pin "52") (pinfunction "HSIP_52") (pintype "passive+no_connect"))
    )
    (net (code "57") (name "unconnected-(U4-HSON-Pad48)") (class "Default")
      (node (ref "U4") (pin "48") (pinfunction "HSON_48") (pintype "passive+no_connect"))
    )
    (net (code "58") (name "unconnected-(U4-HSOP-Pad49)") (class "Default")
      (node (ref "U4") (pin "49") (pinfunction "HSOP_49") (pintype "passive+no_connect"))
    )
    (net (code "59") (name "unconnected-(U4-PAPE_2G_S0-Pad16)") (class "Default")
      (node (ref "U4") (pin "16") (pinfunction "PAPE_2G_S0_16") (pintype "passive+no_connect"))
    )
    (net (code "60") (name "unconnected-(U4-PAPE_2G_S1-Pad64)") (class "Default")
      (node (ref "U4") (pin "64") (pinfunction "PAPE_2G_S1_64") (pintype "passive+no_connect"))
    )
    (net (code "61") (name "unconnected-(U4-RF2IN_S0-Pad4)") (class "Default")
      (node (ref "U4") (pin "4") (pinfunction "RF2IN_S0_4") (pintype "passive+no_connect"))
    )
    (net (code "62") (name "unconnected-(U4-RF2IN_S1-Pad67)") (class "Default")
      (node (ref "U4") (pin "67") (pinfunction "RF2IN_S1_67") (pintype "passive+no_connect"))
    )
    (net (code "63") (name "unconnected-(U4-RF2IP_S0-Pad5)") (class "Default")
      (node (ref "U4") (pin "5") (pinfunction "RF2IP_S0_5") (pintype "passive+no_connect"))
    )
    (net (code "64") (name "unconnected-(U4-RF2IP_S1-Pad68)") (class "Default")
      (node (ref "U4") (pin "68") (pinfunction "RF2IP_S1_68") (pintype "passive+no_connect"))
    )
    (net (code "65") (name "unconnected-(U4-RF2ON_S0-Pad7)") (class "Default")
      (node (ref "U4") (pin "7") (pinfunction "RF2ON_S0_7") (pintype "passive+no_connect"))
    )
    (net (code "66") (name "unconnected-(U4-RF2ON_S1-Pad70)") (class "Default")
      (node (ref "U4") (pin "70") (pinfunction "RF2ON_S1_70") (pintype "passive+no_connect"))
    )
    (net (code "67") (name "unconnected-(U4-RF2OP_S0-Pad8)") (class "Default")
      (node (ref "U4") (pin "8") (pinfunction "RF2OP_S0_8") (pintype "passive+no_connect"))
    )
    (net (code "68") (name "unconnected-(U4-RF2OP_S1-Pad71)") (class "Default")
      (node (ref "U4") (pin "71") (pinfunction "RF2OP_S1_71") (pintype "passive+no_connect"))
    )
    (net (code "69") (name "unconnected-(U4-RF5IN_S0-Pad13)") (class "Default")
      (node (ref "U4") (pin "13") (pinfunction "RF5IN_S0_13") (pintype "passive+no_connect"))
    )
    (net (code "70") (name "unconnected-(U4-RF5IN_S1-Pad76)") (class "Default")
      (node (ref "U4") (pin "76") (pinfunction "RF5IN_S1_76") (pintype "passive+no_connect"))
    )
  )
)
